# MAX485.net
KiCad netlist of a schematic drawn in Altium Designer
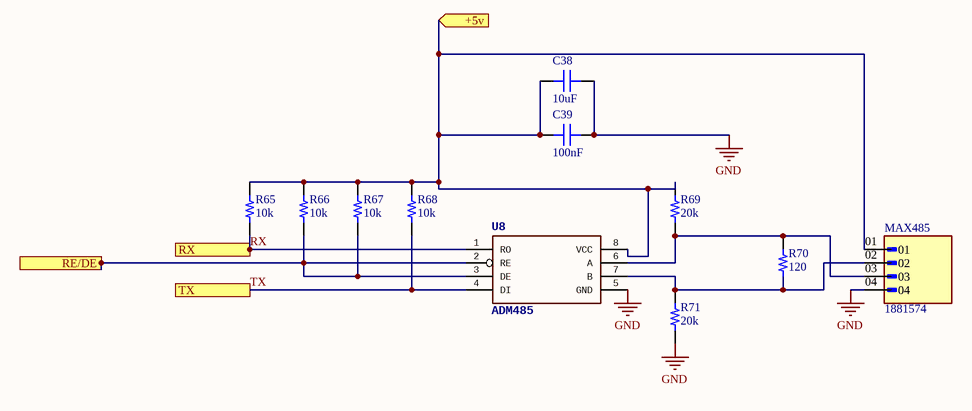
[diagram p0: MAX485.SchDoc]

(export (version "E")
  (design (tool "Eeschema 10.0.6"))
  (components
    (comp (ref "C38")
      (value "10uF")
      (footprint "CAP 0805_2012")
      (description "SMT Capacitor")
      (libsource (lib "Capacitor") (part "Cap 0805"))
    )
    (comp (ref "C39")
      (value "100nF")
      (footprint "CAP 0805_2012")
      (description "SMT Capacitor")
      (libsource (lib "Capacitor") (part "Cap 0805"))
    )
    (comp (ref "MAX485")
      (value "1881574")
      (footprint "PHOENIX_1881574")
      (fields (field (name "MF") "{'manufacturer': u'Phoenix Contact'}"))
      (libsource (lib "1881574") (part "1881574"))
    )
    (comp (ref "R65")
      (value "10k")
      (footprint "RES 0805_2012")
      (description "SMT Resistor")
      (libsource (lib "Resistor") (part "Res 0805"))
    )
    (comp (ref "R66")
      (value "10k")
      (footprint "RES 0805_2012")
      (description "SMT Resistor")
      (libsource (lib "Resistor") (part "Res 0805"))
    )
    (comp (ref "R67")
      (value "10k")
      (footprint "RES 0805_2012")
      (description "SMT Resistor")
      (libsource (lib "Resistor") (part "Res 0805"))
    )
    (comp (ref "R68")
      (value "10k")
      (footprint "RES 0805_2012")
      (description "SMT Resistor")
      (libsource (lib "Resistor") (part "Res 0805"))
    )
    (comp (ref "R69")
      (value "20k")
      (footprint "RES 0805_2012")
      (description "SMT Resistor")
      (libsource (lib "Resistor") (part "Res 0805"))
    )
    (comp (ref "R70")
      (value "120")
      (footprint "RES 0805_2012")
      (description "SMT Resistor")
      (libsource (lib "Resistor") (part "Res 0805"))
    )
    (comp (ref "R71")
      (value "20k")
      (footprint "RES 0805_2012")
      (description "SMT Resistor")
      (libsource (lib "Resistor") (part "Res 0805"))
    )
    (comp (ref "U8")
      (value "ADM485")
      (footprint "SOIC-8 4.9X3.9MM P1.27MM")
      (description "RS485 Interface")
      (fields (field (name "PARTNUMBER") "ADM4853ARZ-REEL7"))
      (libsource (lib "Chip") (part "ADM485 (SMD)"))
    )
  )
  (nets
    (net (code "1") (name "/+5v") (class "Default")
      (node (ref "C38") (pin "1") (pinfunction "1_1") (pintype "passive"))
      (node (ref "C39") (pin "1") (pinfunction "1_1") (pintype "passive"))
      (node (ref "MAX485") (pin "01") (pinfunction "01_01") (pintype "passive"))
      (node (ref "R65") (pin "2") (pinfunction "2_2") (pintype "passive"))
      (node (ref "R66") (pin "2") (pinfunction "2_2") (pintype "passive"))
      (node (ref "R67") (pin "2") (pinfunction "2_2") (pintype "passive"))
      (node (ref "R68") (pin "2") (pinfunction "2_2") (pintype "passive"))
      (node (ref "R69") (pin "2") (pinfunction "2_2") (pintype "passive"))
      (node (ref "U8") (pin "8") (pinfunction "VCC_8") (pintype "passive"))
    )
    (net (code "2") (name "/RE{slash}DE") (class "Default")
      (node (ref "R66") (pin "1") (pinfunction "1_1") (pintype "passive"))
      (node (ref "R67") (pin "1") (pinfunction "1_1") (pintype "passive"))
      (node (ref "U8") (pin "2") (pinfunction "RE_2") (pintype "passive"))
      (node (ref "U8") (pin "3") (pinfunction "DE_3") (pintype "passive"))
    )
    (net (code "3") (name "/RX") (class "Default")
      (node (ref "R65") (pin "1") (pinfunction "1_1") (pintype "passive"))
      (node (ref "U8") (pin "1") (pinfunction "RO_1") (pintype "passive"))
    )
    (net (code "4") (name "/TX") (class "Default")
      (node (ref "R68") (pin "1") (pinfunction "1_1") (pintype "passive"))
      (node (ref "U8") (pin "4") (pinfunction "DI_4") (pintype "passive"))
    )
    (net (code "5") (name "GND") (class "Default")
      (node (ref "C38") (pin "2") (pinfunction "2_2") (pintype "passive"))
      (node (ref "C39") (pin "2") (pinfunction "2_2") (pintype "passive"))
      (node (ref "MAX485") (pin "04") (pinfunction "04_04") (pintype "passive"))
      (node (ref "R71") (pin "1") (pinfunction "1_1") (pintype "passive"))
      (node (ref "U8") (pin "5") (pinfunction "GND_5") (pintype "passive"))
    )
    (net (code "6") (name "Net-(U8-A)") (class "Default")
      (node (ref "MAX485") (pin "03") (pinfunction "03_03") (pintype "passive"))
      (node (ref "R69") (pin "1") (pinfunction "1_1") (pintype "passive"))
      (node (ref "R70") (pin "2") (pinfunction "2_2") (pintype "passive"))
      (node (ref "U8") (pin "6") (pinfunction "A_6") (pintype "passive"))
    )
    (net (code "7") (name "Net-(U8-B)") (class "Default")
      (node (ref "MAX485") (pin "02") (pinfunction "02_02") (pintype "passive"))
      (node (ref "R70") (pin "1") (pinfunction "1_1") (pintype "passive"))
      (node (ref "R71") (pin "2") (pinfunction "2_2") (pintype "passive"))
      (node (ref "U8") (pin "7") (pinfunction "B_7") (pintype "passive"))
    )
  )
)
